# mems_quart_board_ics_40720.net
KiCad netlist of a schematic drawn in EAGLE
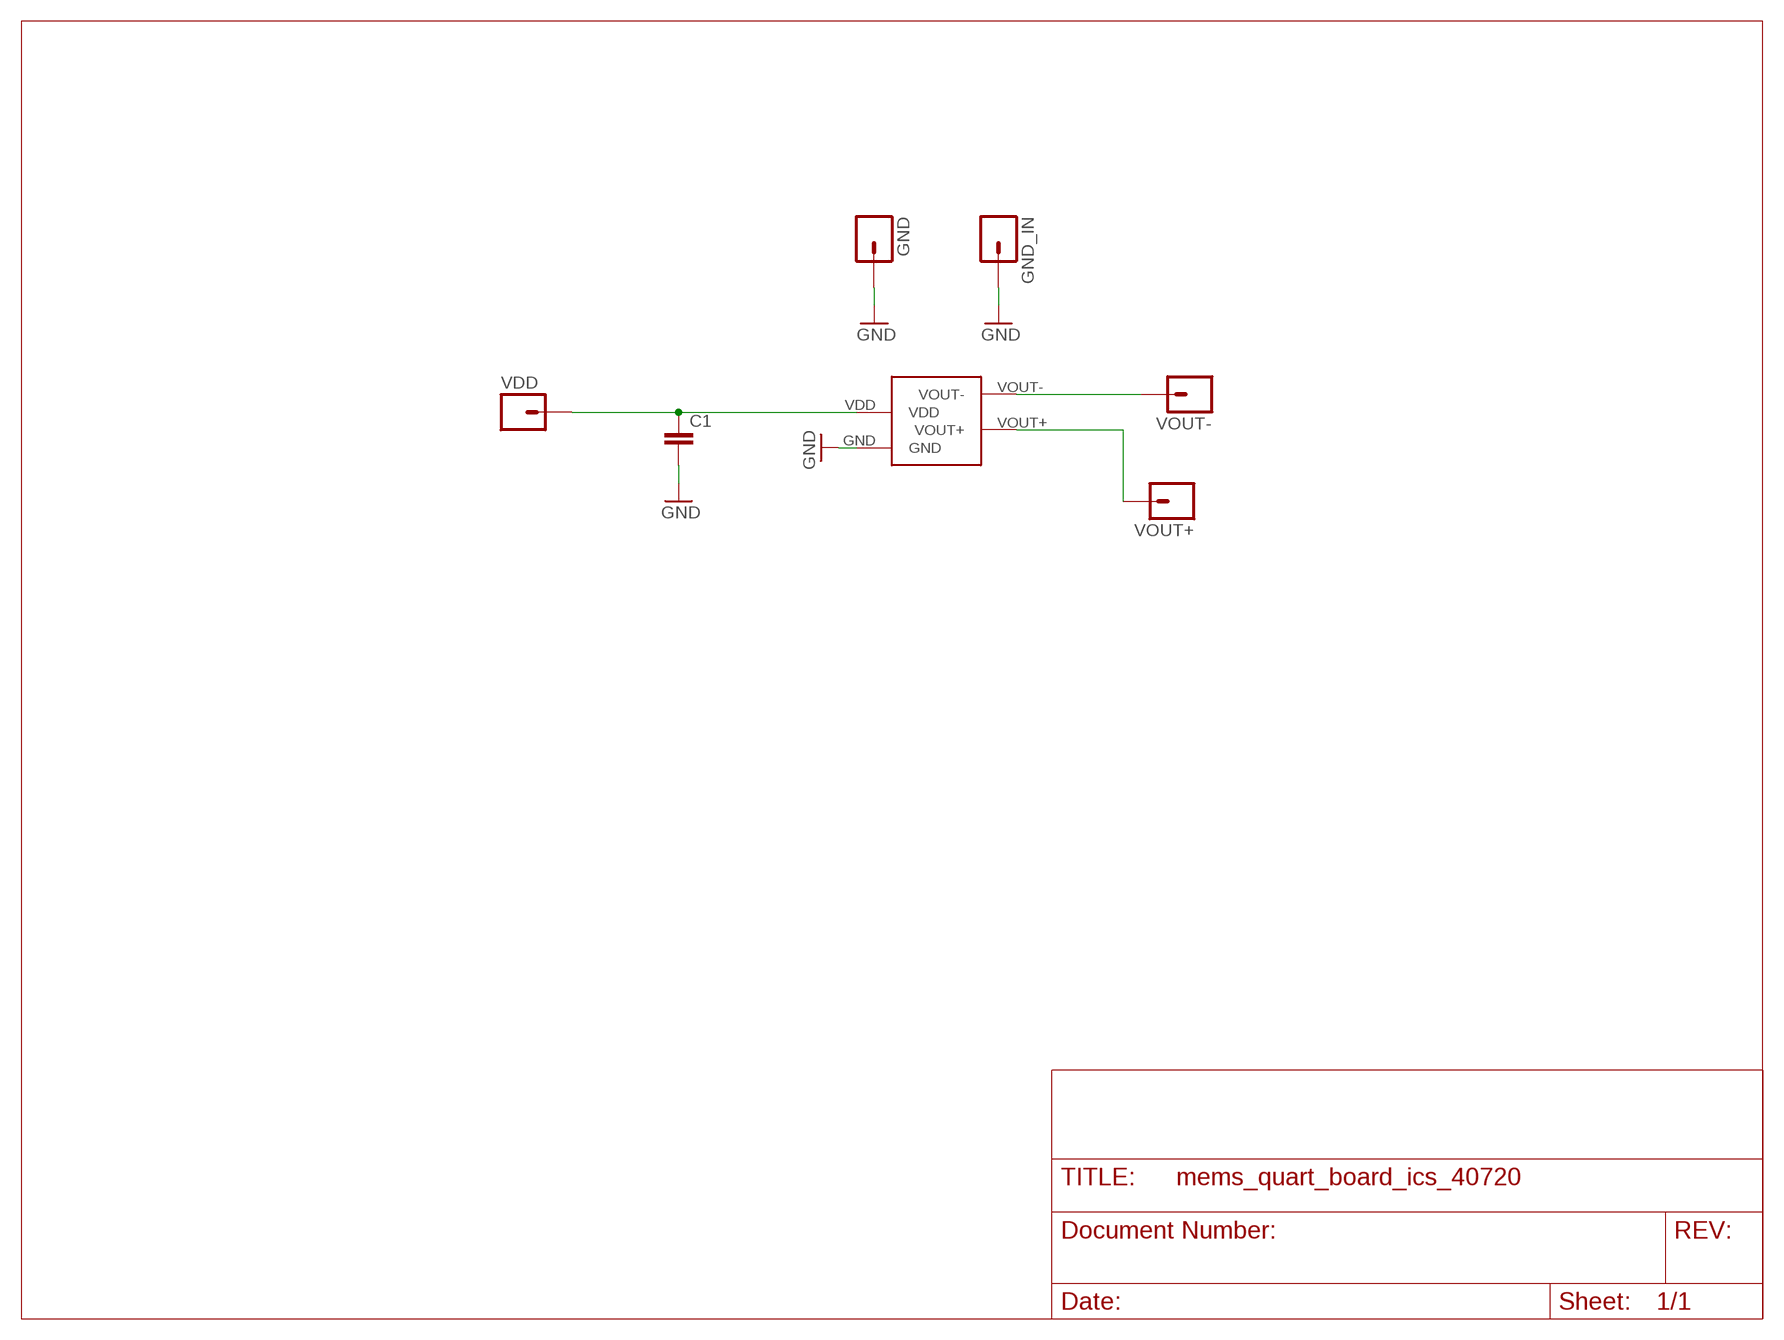
[diagram p0: schematic, sheet 1]

(export (version "E")
  (design (tool "Eeschema 10.0.6"))
  (components
    (comp (ref "C1")
      (value "0.1UF-16V(+-10%)(0402)")
      (footprint "eagle-import:0402-CAP")
      (libsource (lib "eagle-import") (part "0.1UF-16V(+-10%)(0402)"))
    )
    (comp (ref "GND")
      (value "M01PTH_NO_SILK_YES_STOP")
      (footprint "eagle-import:1X01_NO_SILK")
      (libsource (lib "eagle-import") (part "CM-SparkFun-Connectors-large_hole_M01PTH_NO_SILK_YES_STOP"))
    )
    (comp (ref "GND_IN")
      (value "M01NOSILK-KIT")
      (footprint "eagle-import:1X01NS-KIT")
      (libsource (lib "eagle-import") (part "M01NOSILK-KIT"))
    )
    (comp (ref "U$1")
      (value "MEMS_ICS_40720")
      (footprint "eagle-import: MEMS_ICS_40720")
      (libsource (lib "eagle-import") (part " MEMS_ICS_40720"))
    )
    (comp (ref "VDD")
      (value "M01NOSILK-KIT")
      (footprint "eagle-import:1X01NS-KIT")
      (libsource (lib "eagle-import") (part "M01NOSILK-KIT"))
    )
    (comp (ref "VOUT+")
      (value "M01NOSILK-KIT")
      (footprint "eagle-import:1X01NS-KIT")
      (libsource (lib "eagle-import") (part "M01NOSILK-KIT"))
    )
    (comp (ref "VOUT-")
      (value "M01NOSILK-KIT")
      (footprint "eagle-import:1X01NS-KIT")
      (libsource (lib "eagle-import") (part "M01NOSILK-KIT"))
    )
  )
  (nets
    (net (code "1") (name "GND") (class "Default")
      (node (ref "C1") (pin "2") (pinfunction "2_2") (pintype "passive"))
      (node (ref "GND") (pin "1") (pinfunction "1_1") (pintype "passive"))
      (node (ref "GND_IN") (pin "1") (pinfunction "1_1") (pintype "passive"))
      (node (ref "U$1") (pin "GND") (pinfunction "GND_GND") (pintype "input"))
    )
    (net (code "2") (name "Net-(C1-Pad1)") (class "Default")
      (node (ref "C1") (pin "1") (pinfunction "1_1") (pintype "passive"))
      (node (ref "U$1") (pin "VDD") (pinfunction "VDD_VDD") (pintype "power_in"))
      (node (ref "VDD") (pin "1") (pinfunction "1_1") (pintype "passive"))
    )
    (net (code "3") (name "Net-(U$1-PadVOUT+)") (class "Default")
      (node (ref "U$1") (pin "VOUT+") (pinfunction "VOUT+_VOUT+") (pintype "input"))
      (node (ref "VOUT+") (pin "1") (pinfunction "1_1") (pintype "passive"))
    )
    (net (code "4") (name "Net-(U$1-PadVOUT-)") (class "Default")
      (node (ref "U$1") (pin "VOUT-") (pinfunction "VOUT-_VOUT-") (pintype "input"))
      (node (ref "VOUT-") (pin "1") (pinfunction "1_1") (pintype "passive"))
    )
  )
)
